# FPGA_GPIO.net
KiCad netlist of a schematic drawn in Altium Designer
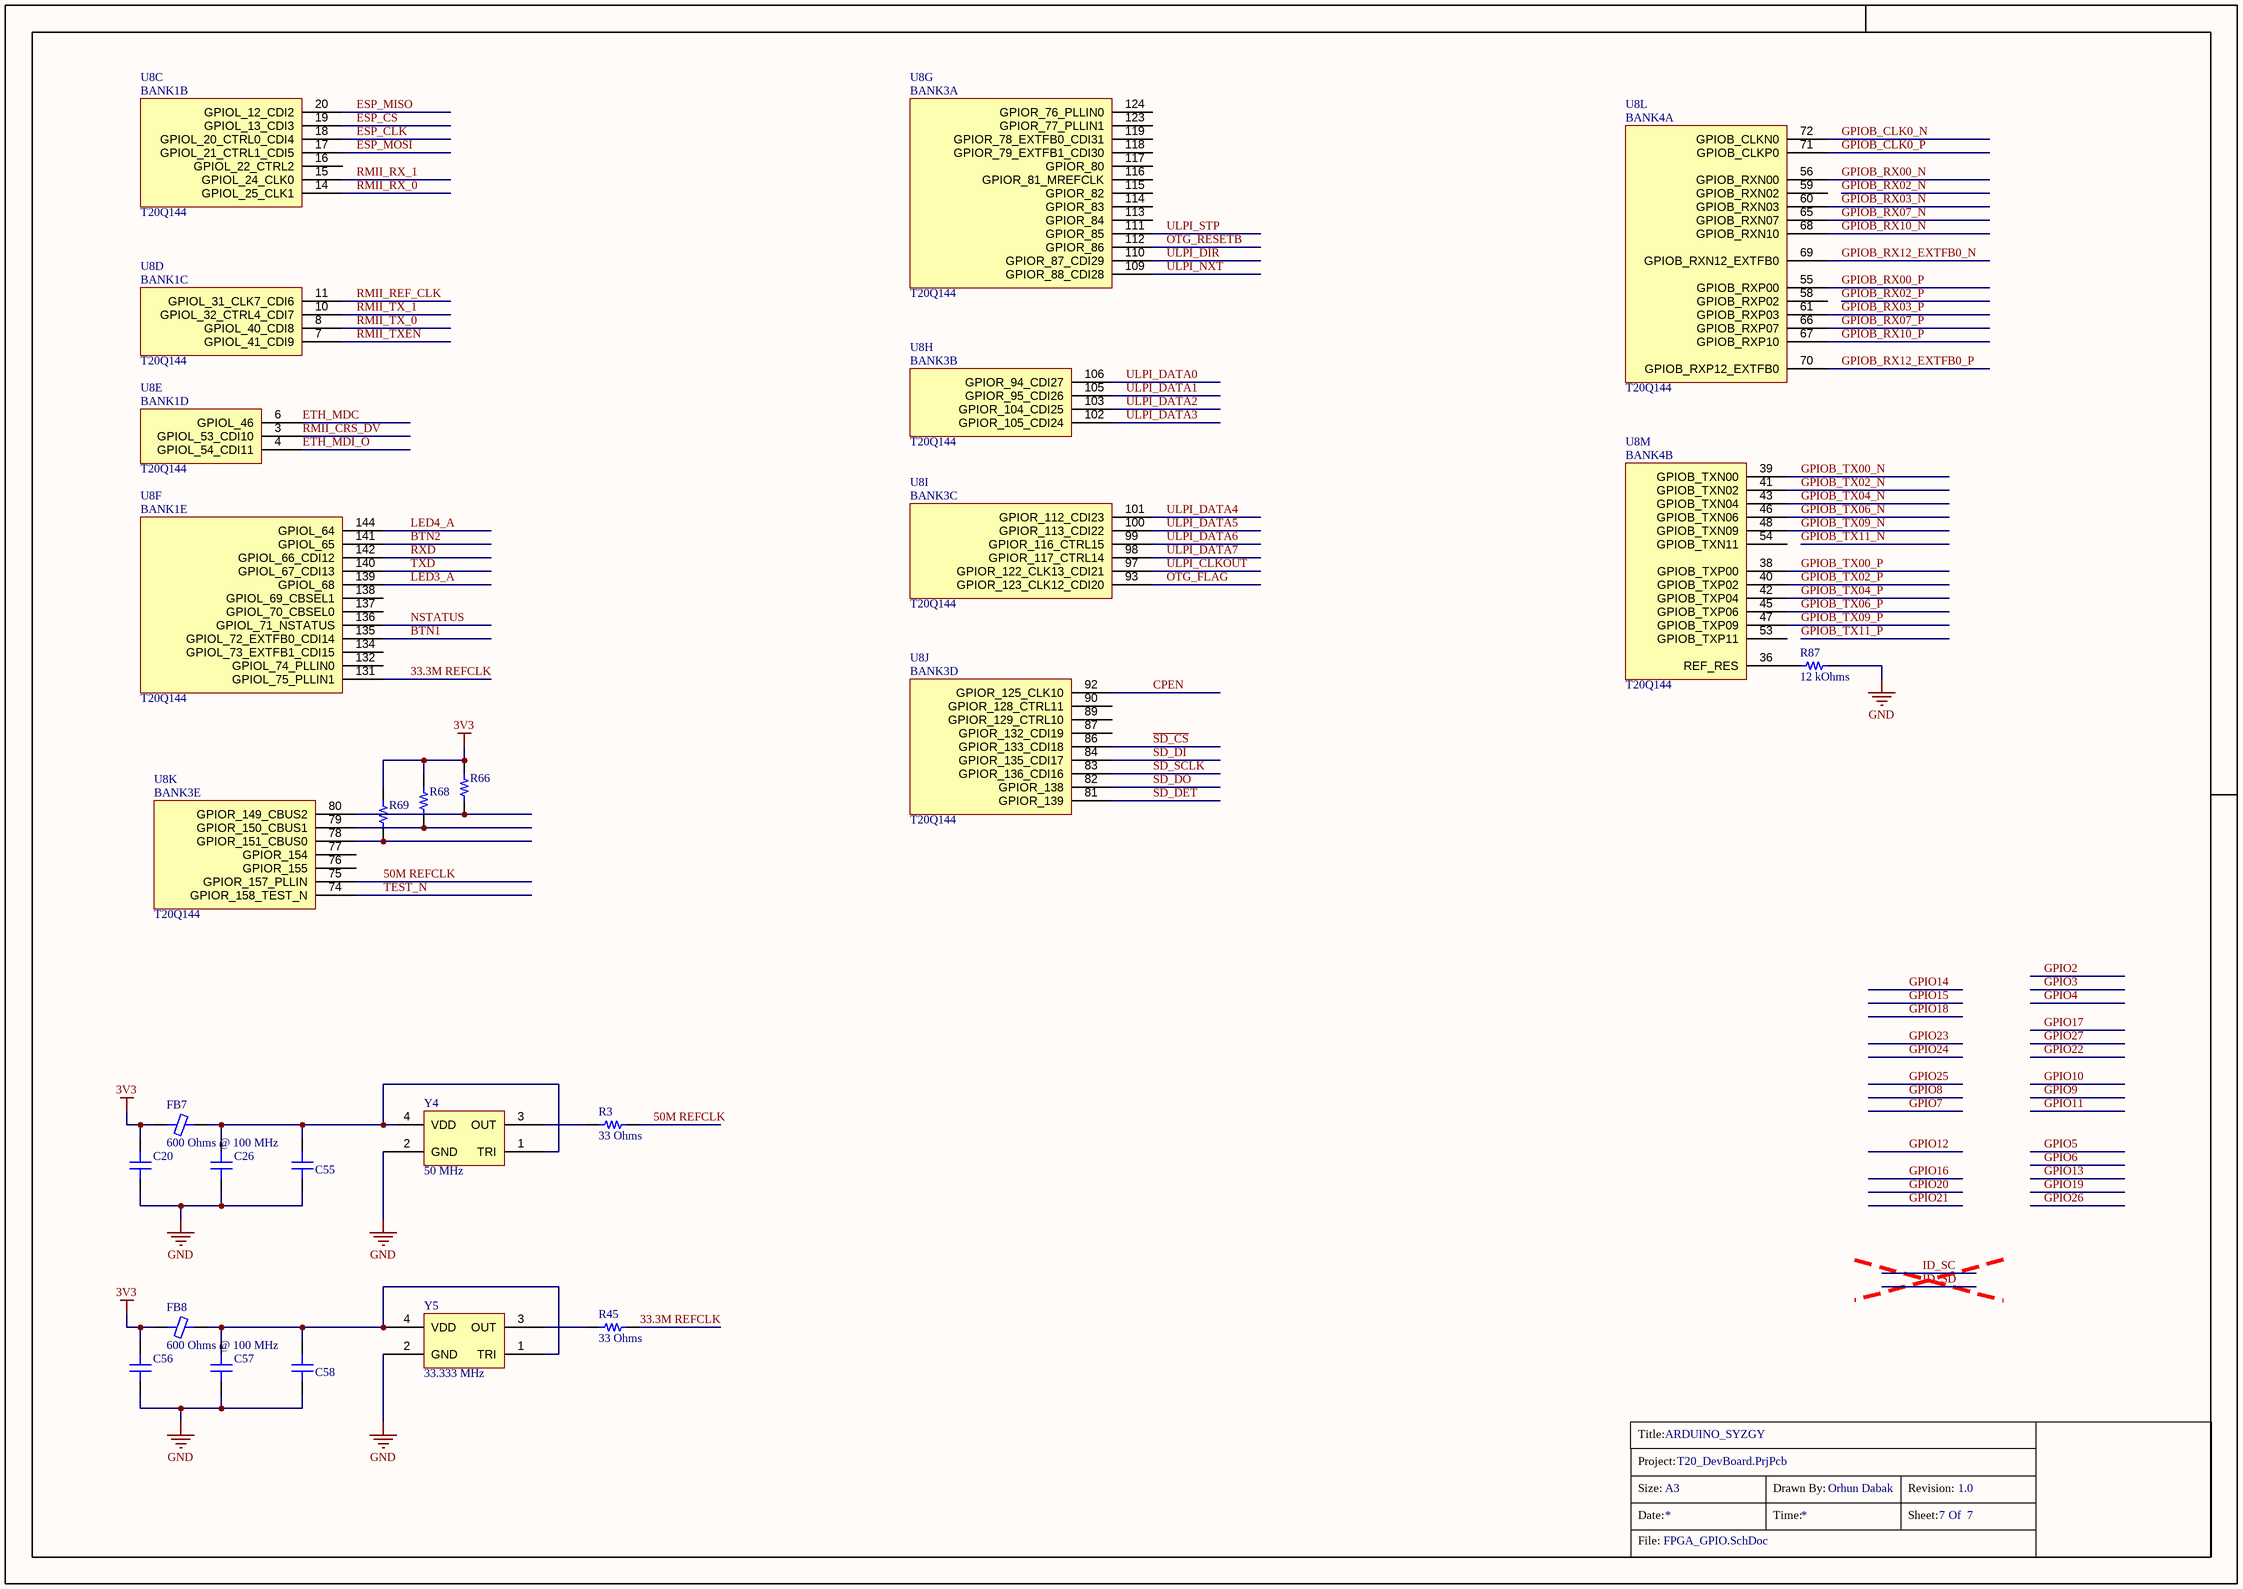
[diagram p0: FPGA_GPIO.SchDoc]

(export (version "E")
  (design (tool "Eeschema 10.0.6"))
  (components
    (comp (ref "C20")
      (value "4.7 µF")
      (footprint "CAP 0402_1005")
      (description "CAP CER 4.7UF 10V X5R 0402")
      (fields
        (field (name "PART NUMBER") "CL05A475MP5NRNC")
        (field (name "MANUFACTURER") "Samsung Electro-Mechanics")
      )
      (libsource (lib "Celestial Altium Library - altium_library") (part "Capacitor"))
    )
    (comp (ref "C26")
      (value "4.7 µF")
      (footprint "CAP 0402_1005")
      (description "CAP CER 4.7UF 10V X5R 0402")
      (fields
        (field (name "PART NUMBER") "CL05A475MP5NRNC")
        (field (name "MANUFACTURER") "Samsung Electro-Mechanics")
      )
      (libsource (lib "Celestial Altium Library - altium_library") (part "Capacitor"))
    )
    (comp (ref "C55")
      (value "10000 pF")
      (footprint "CAP 0402_1005")
      (description "CAP CER 0402 10NF 50V X7R 10%")
      (fields (field (name "PART NUMBER") "C0402C103K5RECAUTO") (field (name "MANUFACTURER") "KEMET"))
      (libsource (lib "Celestial Altium Library - altium_library") (part "Capacitor"))
    )
    (comp (ref "C56")
      (value "4.7 µF")
      (footprint "CAP 0402_1005")
      (description "CAP CER 4.7UF 10V X5R 0402")
      (fields
        (field (name "PART NUMBER") "CL05A475MP5NRNC")
        (field (name "MANUFACTURER") "Samsung Electro-Mechanics")
      )
      (libsource (lib "Celestial Altium Library - altium_library") (part "Capacitor"))
    )
    (comp (ref "C57")
      (value "4.7 µF")
      (footprint "CAP 0402_1005")
      (description "CAP CER 4.7UF 10V X5R 0402")
      (fields
        (field (name "PART NUMBER") "CL05A475MP5NRNC")
        (field (name "MANUFACTURER") "Samsung Electro-Mechanics")
      )
      (libsource (lib "Celestial Altium Library - altium_library") (part "Capacitor"))
    )
    (comp (ref "C58")
      (value "10000 pF")
      (footprint "CAP 0402_1005")
      (description "CAP CER 0402 10NF 50V X7R 10%")
      (fields (field (name "PART NUMBER") "C0402C103K5RECAUTO") (field (name "MANUFACTURER") "KEMET"))
      (libsource (lib "Celestial Altium Library - altium_library") (part "Capacitor"))
    )
    (comp (ref "FB7")
      (value "600 Ohms @ 100 MHz")
      (footprint "FER 0402_1005")
      (description "FERRITE BEAD 600 OHM 0402 1LN")
      (fields
        (field (name "PART NUMBER") "BLM15AG601SN1D")
        (field (name "MANUFACTURER") "Murata Electronics")
      )
      (libsource (lib "Celestial Altium Library - altium_library") (part "Ferrite Chip"))
    )
    (comp (ref "FB8")
      (value "600 Ohms @ 100 MHz")
      (footprint "FER 0402_1005")
      (description "FERRITE BEAD 600 OHM 0402 1LN")
      (fields
        (field (name "PART NUMBER") "BLM15AG601SN1D")
        (field (name "MANUFACTURER") "Murata Electronics")
      )
      (libsource (lib "Celestial Altium Library - altium_library") (part "Ferrite Chip"))
    )
    (comp (ref "R3")
      (value "33 Ohms")
      (footprint "RES 0402_1005")
      (description "RES 33 OHM 1% 1/16W 0402")
      (fields (field (name "PART NUMBER") "RC0402FR-0733RL") (field (name "MANUFACTURER") "Yageo"))
      (libsource (lib "Celestial Altium Library - altium_library") (part "Resistor"))
    )
    (comp (ref "R45")
      (value "33 Ohms")
      (footprint "RES 0402_1005")
      (description "RES 33 OHM 1% 1/16W 0402")
      (fields (field (name "PART NUMBER") "RC0402FR-0733RL") (field (name "MANUFACTURER") "Yageo"))
      (libsource (lib "Celestial Altium Library - altium_library") (part "Resistor"))
    )
    (comp (ref "R66")
      (value "10 kOhms")
      (footprint "RES 0402_1005")
      (description "RES 10K OHM 0.1% 1/10W 0402")
      (fields
        (field (name "PART NUMBER") "RP73PF1E10KBTD")
        (field (name "MANUFACTURER") "TE Connectivity Passive Product")
      )
      (libsource (lib "Celestial Altium Library - altium_library") (part "Resistor"))
    )
    (comp (ref "R68")
      (value "10 kOhms")
      (footprint "RES 0402_1005")
      (description "RES 10K OHM 0.1% 1/10W 0402")
      (fields
        (field (name "PART NUMBER") "RP73PF1E10KBTD")
        (field (name "MANUFACTURER") "TE Connectivity Passive Product")
      )
      (libsource (lib "Celestial Altium Library - altium_library") (part "Resistor"))
    )
    (comp (ref "R69")
      (value "10 kOhms")
      (footprint "RES 0402_1005")
      (description "RES 10K OHM 0.1% 1/10W 0402")
      (fields
        (field (name "PART NUMBER") "RP73PF1E10KBTD")
        (field (name "MANUFACTURER") "TE Connectivity Passive Product")
      )
      (libsource (lib "Celestial Altium Library - altium_library") (part "Resistor"))
    )
    (comp (ref "R87")
      (value "12 kOhms")
      (footprint "RES 0402_1005")
      (description "RES 12K OHM 1% 1/16W 0402")
      (fields
        (field (name "PART NUMBER") "RMCF0402FT12K0")
        (field (name "MANUFACTURER") "Stackpole Electronics Inc")
      )
      (libsource (lib "Celestial Altium Library - altium_library") (part "Resistor"))
    )
    (comp (ref "U8")
      (value "T20Q144")
      (footprint "T8_devkit_PCB:CQFP50P2200X2200X160-144N")
      (description "Trion® Field Programmable Gate Array (FPGA) IC 97 1044 19728 144-LQFP")
      (libsource (lib "T8_devkit_PCB") (part "T20Q144"))
    )
    (comp (ref "Y4")
      (value "50 MHz")
      (footprint "ABRACON ASE")
      (description "XTAL OSC XO 50.0000MHZ CMOS SMD")
      (fields (field (name "PART NUMBER") "ASE-50.000MHZ-ET") (field (name "MANUFACTURER") "Abracon LLC"))
      (libsource (lib "Celestial Altium Library - altium_library") (part "Abracon XO ASE"))
    )
    (comp (ref "Y5")
      (value "33.333 MHz")
      (footprint "ABRACON ASE")
      (description "XTAL OSC XO 33.3330MHZ CMOS SMD")
      (fields (field (name "PART NUMBER") "ASE-33.333MHZ-LC-T") (field (name "MANUFACTURER") "Abracon LLC"))
      (libsource (lib "Celestial Altium Library - altium_library") (part "Abracon XO ASE"))
    )
  )
  (nets
    (net (code "1") (name "/33.3M REFCLK") (class "Default")
      (node (ref "R45") (pin "2") (pinfunction "2_2") (pintype "passive"))
      (node (ref "U8") (pin "131") (pinfunction "GPIOL_75_PLLIN1_131") (pintype "passive"))
    )
    (net (code "2") (name "/50M REFCLK") (class "Default")
      (node (ref "R3") (pin "2") (pinfunction "2_2") (pintype "passive"))
      (node (ref "U8") (pin "75") (pinfunction "GPIOR_157_PLLIN_75") (pintype "passive"))
    )
    (net (code "3") (name "/BTN1") (class "Default")
      (node (ref "U8") (pin "135") (pinfunction "GPIOL_72_EXTFB0_CDI14_135") (pintype "passive"))
    )
    (net (code "4") (name "/BTN2") (class "Default")
      (node (ref "U8") (pin "141") (pinfunction "GPIOL_65_141") (pintype "passive"))
    )
    (net (code "5") (name "/CPEN") (class "Default")
      (node (ref "U8") (pin "92") (pinfunction "GPIOR_125_CLK10_92") (pintype "passive"))
    )
    (net (code "6") (name "/ESP_CLK") (class "Default")
      (node (ref "U8") (pin "18") (pinfunction "GPIOL_20_CTRL0_CDI4_18") (pintype "passive"))
    )
    (net (code "7") (name "/ESP_CS") (class "Default")
      (node (ref "U8") (pin "19") (pinfunction "GPIOL_13_CDI3_19") (pintype "passive"))
    )
    (net (code "8") (name "/ESP_MISO") (class "Default")
      (node (ref "U8") (pin "20") (pinfunction "GPIOL_12_CDI2_20") (pintype "passive"))
    )
    (net (code "9") (name "/ESP_MOSI") (class "Default")
      (node (ref "U8") (pin "17") (pinfunction "GPIOL_21_CTRL1_CDI5_17") (pintype "passive"))
    )
    (net (code "10") (name "/ETH_MDC") (class "Default")
      (node (ref "U8") (pin "6") (pinfunction "GPIOL_46_6") (pintype "passive"))
    )
    (net (code "11") (name "/ETH_MDI_O") (class "Default")
      (node (ref "U8") (pin "4") (pinfunction "GPIOL_54_CDI11_4") (pintype "passive"))
    )
    (net (code "38") (name "/GPIOB_CLK0_N") (class "Default")
      (node (ref "U8") (pin "72") (pinfunction "GPIOB_CLKN0_72") (pintype "passive"))
    )
    (net (code "39") (name "/GPIOB_CLK0_P") (class "Default")
      (node (ref "U8") (pin "71") (pinfunction "GPIOB_CLKP0_71") (pintype "passive"))
    )
    (net (code "40") (name "/GPIOB_RX00_N") (class "Default")
      (node (ref "U8") (pin "56") (pinfunction "GPIOB_RXN00_56") (pintype "passive"))
    )
    (net (code "41") (name "/GPIOB_RX00_P") (class "Default")
      (node (ref "U8") (pin "55") (pinfunction "GPIOB_RXP00_55") (pintype "passive"))
    )
    (net (code "44") (name "/GPIOB_RX03_N") (class "Default")
      (node (ref "U8") (pin "60") (pinfunction "GPIOB_RXN03_60") (pintype "passive"))
    )
    (net (code "45") (name "/GPIOB_RX03_P") (class "Default")
      (node (ref "U8") (pin "61") (pinfunction "GPIOB_RXP03_61") (pintype "passive"))
    )
    (net (code "46") (name "/GPIOB_RX07_N") (class "Default")
      (node (ref "U8") (pin "65") (pinfunction "GPIOB_RXN07_65") (pintype "passive"))
    )
    (net (code "47") (name "/GPIOB_RX07_P") (class "Default")
      (node (ref "U8") (pin "66") (pinfunction "GPIOB_RXP07_66") (pintype "passive"))
    )
    (net (code "48") (name "/GPIOB_RX10_N") (class "Default")
      (node (ref "U8") (pin "68") (pinfunction "GPIOB_RXN10_68") (pintype "passive"))
    )
    (net (code "49") (name "/GPIOB_RX10_P") (class "Default")
      (node (ref "U8") (pin "67") (pinfunction "GPIOB_RXP10_67") (pintype "passive"))
    )
    (net (code "50") (name "/GPIOB_RX12_EXTFB0_N") (class "Default")
      (node (ref "U8") (pin "69") (pinfunction "GPIOB_RXN12_EXTFB0_69") (pintype "passive"))
    )
    (net (code "51") (name "/GPIOB_RX12_EXTFB0_P") (class "Default")
      (node (ref "U8") (pin "70") (pinfunction "GPIOB_RXP12_EXTFB0_70") (pintype "passive"))
    )
    (net (code "52") (name "/GPIOB_TX00_N") (class "Default")
      (node (ref "U8") (pin "39") (pinfunction "GPIOB_TXN00_39") (pintype "passive"))
    )
    (net (code "53") (name "/GPIOB_TX00_P") (class "Default")
      (node (ref "U8") (pin "38") (pinfunction "GPIOB_TXP00_38") (pintype "passive"))
    )
    (net (code "54") (name "/GPIOB_TX02_N") (class "Default")
      (node (ref "U8") (pin "41") (pinfunction "GPIOB_TXN02_41") (pintype "passive"))
    )
    (net (code "55") (name "/GPIOB_TX02_P") (class "Default")
      (node (ref "U8") (pin "40") (pinfunction "GPIOB_TXP02_40") (pintype "passive"))
    )
    (net (code "56") (name "/GPIOB_TX04_N") (class "Default")
      (node (ref "U8") (pin "43") (pinfunction "GPIOB_TXN04_43") (pintype "passive"))
    )
    (net (code "57") (name "/GPIOB_TX04_P") (class "Default")
      (node (ref "U8") (pin "42") (pinfunction "GPIOB_TXP04_42") (pintype "passive"))
    )
    (net (code "58") (name "/GPIOB_TX06_N") (class "Default")
      (node (ref "U8") (pin "46") (pinfunction "GPIOB_TXN06_46") (pintype "passive"))
    )
    (net (code "59") (name "/GPIOB_TX06_P") (class "Default")
      (node (ref "U8") (pin "45") (pinfunction "GPIOB_TXP06_45") (pintype "passive"))
    )
    (net (code "60") (name "/GPIOB_TX09_N") (class "Default")
      (node (ref "U8") (pin "48") (pinfunction "GPIOB_TXN09_48") (pintype "passive"))
    )
    (net (code "61") (name "/GPIOB_TX09_P") (class "Default")
      (node (ref "U8") (pin "47") (pinfunction "GPIOB_TXP09_47") (pintype "passive"))
    )
    (net (code "66") (name "/LED3_A") (class "Default")
      (node (ref "U8") (pin "139") (pinfunction "GPIOL_68_139") (pintype "passive"))
    )
    (net (code "67") (name "/LED4_A") (class "Default")
      (node (ref "U8") (pin "144") (pinfunction "GPIOL_64_144") (pintype "passive"))
    )
    (net (code "68") (name "/NSTATUS") (class "Default")
      (node (ref "U8") (pin "136") (pinfunction "GPIOL_71_NSTATUS_136") (pintype "passive"))
    )
    (net (code "69") (name "/OTG_FLAG") (class "Default")
      (node (ref "U8") (pin "93") (pinfunction "GPIOR_123_CLK12_CDI20_93") (pintype "passive"))
    )
    (net (code "70") (name "/OTG_RESETB") (class "Default")
      (node (ref "U8") (pin "112") (pinfunction "GPIOR_86_112") (pintype "passive"))
    )
    (net (code "71") (name "/RMII_CRS_DV") (class "Default")
      (node (ref "U8") (pin "3") (pinfunction "GPIOL_53_CDI10_3") (pintype "passive"))
    )
    (net (code "72") (name "/RMII_REF_CLK") (class "Default")
      (node (ref "U8") (pin "11") (pinfunction "GPIOL_31_CLK7_CDI6_11") (pintype "passive"))
    )
    (net (code "73") (name "/RMII_RX_0") (class "Default")
      (node (ref "U8") (pin "14") (pinfunction "GPIOL_25_CLK1_14") (pintype "passive"))
    )
    (net (code "74") (name "/RMII_RX_1") (class "Default")
      (node (ref "U8") (pin "15") (pinfunction "GPIOL_24_CLK0_15") (pintype "passive"))
    )
    (net (code "75") (name "/RMII_TXEN") (class "Default")
      (node (ref "U8") (pin "7") (pinfunction "GPIOL_41_CDI9_7") (pintype "passive"))
    )
    (net (code "76") (name "/RMII_TX_0") (class "Default")
      (node (ref "U8") (pin "8") (pinfunction "GPIOL_40_CDI8_8") (pintype "passive"))
    )
    (net (code "77") (name "/RMII_TX_1") (class "Default")
      (node (ref "U8") (pin "10") (pinfunction "GPIOL_32_CTRL4_CDI7_10") (pintype "passive"))
    )
    (net (code "78") (name "/RXD") (class "Default")
      (node (ref "U8") (pin "142") (pinfunction "GPIOL_66_CDI12_142") (pintype "passive"))
    )
    (net (code "79") (name "/SD_DI") (class "Default")
      (node (ref "U8") (pin "84") (pinfunction "GPIOR_135_CDI17_84") (pintype "passive"))
    )
    (net (code "80") (name "/SD_DO") (class "Default")
      (node (ref "U8") (pin "82") (pinfunction "GPIOR_138_82") (pintype "passive"))
    )
    (net (code "81") (name "/SD_SCLK") (class "Default")
      (node (ref "U8") (pin "83") (pinfunction "GPIOR_136_CDI16_83") (pintype "passive"))
    )
    (net (code "82") (name "/TEST_N") (class "Default")
      (node (ref "U8") (pin "74") (pinfunction "GPIOR_158_TEST_N_74") (pintype "passive"))
    )
    (net (code "83") (name "/TXD") (class "Default")
      (node (ref "U8") (pin "140") (pinfunction "GPIOL_67_CDI13_140") (pintype "passive"))
    )
    (net (code "84") (name "/ULPI_CLKOUT") (class "Default")
      (node (ref "U8") (pin "97") (pinfunction "GPIOR_122_CLK13_CDI21_97") (pintype "passive"))
    )
    (net (code "85") (name "/ULPI_DATA0") (class "Default")
      (node (ref "U8") (pin "106") (pinfunction "GPIOR_94_CDI27_106") (pintype "passive"))
    )
    (net (code "86") (name "/ULPI_DATA1") (class "Default")
      (node (ref "U8") (pin "105") (pinfunction "GPIOR_95_CDI26_105") (pintype "passive"))
    )
    (net (code "87") (name "/ULPI_DATA2") (class "Default")
      (node (ref "U8") (pin "103") (pinfunction "GPIOR_104_CDI25_103") (pintype "passive"))
    )
    (net (code "88") (name "/ULPI_DATA3") (class "Default")
      (node (ref "U8") (pin "102") (pinfunction "GPIOR_105_CDI24_102") (pintype "passive"))
    )
    (net (code "89") (name "/ULPI_DATA4") (class "Default")
      (node (ref "U8") (pin "101") (pinfunction "GPIOR_112_CDI23_101") (pintype "passive"))
    )
    (net (code "90") (name "/ULPI_DATA5") (class "Default")
      (node (ref "U8") (pin "100") (pinfunction "GPIOR_113_CDI22_100") (pintype "passive"))
    )
    (net (code "91") (name "/ULPI_DATA6") (class "Default")
      (node (ref "U8") (pin "99") (pinfunction "GPIOR_116_CTRL15_99") (pintype "passive"))
    )
    (net (code "92") (name "/ULPI_DATA7") (class "Default")
      (node (ref "U8") (pin "98") (pinfunction "GPIOR_117_CTRL14_98") (pintype "passive"))
    )
    (net (code "93") (name "/ULPI_DIR") (class "Default")
      (node (ref "U8") (pin "110") (pinfunction "GPIOR_87_CDI29_110") (pintype "passive"))
    )
    (net (code "94") (name "/ULPI_NXT") (class "Default")
      (node (ref "U8") (pin "109") (pinfunction "GPIOR_88_CDI28_109") (pintype "passive"))
    )
    (net (code "95") (name "/ULPI_STP") (class "Default")
      (node (ref "U8") (pin "111") (pinfunction "GPIOR_85_111") (pintype "passive"))
    )
    (net (code "96") (name "/~{SD_CS}") (class "Default")
      (node (ref "U8") (pin "86") (pinfunction "GPIOR_133_CDI18_86") (pintype "passive"))
    )
    (net (code "97") (name "/~{SD_DET}") (class "Default")
      (node (ref "U8") (pin "81") (pinfunction "GPIOR_139_81") (pintype "passive"))
    )
    (net (code "98") (name "3V3") (class "Default")
      (node (ref "C20") (pin "2") (pinfunction "2_2") (pintype "passive"))
      (node (ref "C56") (pin "2") (pinfunction "2_2") (pintype "passive"))
      (node (ref "FB7") (pin "1") (pinfunction "1_1") (pintype "passive"))
      (node (ref "FB8") (pin "1") (pinfunction "1_1") (pintype "passive"))
      (node (ref "R66") (pin "2") (pinfunction "2_2") (pintype "passive"))
      (node (ref "R68") (pin "2") (pinfunction "2_2") (pintype "passive"))
      (node (ref "R69") (pin "2") (pinfunction "2_2") (pintype "passive"))
    )
    (net (code "99") (name "GND") (class "Default")
      (node (ref "C20") (pin "1") (pinfunction "1_1") (pintype "passive"))
      (node (ref "C26") (pin "1") (pinfunction "1_1") (pintype "passive"))
      (node (ref "C55") (pin "1") (pinfunction "1_1") (pintype "passive"))
      (node (ref "C56") (pin "1") (pinfunction "1_1") (pintype "passive"))
      (node (ref "C57") (pin "1") (pinfunction "1_1") (pintype "passive"))
      (node (ref "C58") (pin "1") (pinfunction "1_1") (pintype "passive"))
      (node (ref "R87") (pin "2") (pinfunction "2_2") (pintype "passive"))
      (node (ref "Y4") (pin "2") (pinfunction "GND_2") (pintype "passive"))
      (node (ref "Y5") (pin "2") (pinfunction "GND_2") (pintype "passive"))
    )
    (net (code "100") (name "Net-(U8K-GPIOR_149_CBUS2)") (class "Default")
      (node (ref "R66") (pin "1") (pinfunction "1_1") (pintype "passive"))
      (node (ref "U8") (pin "80") (pinfunction "GPIOR_149_CBUS2_80") (pintype "passive"))
    )
    (net (code "101") (name "Net-(U8K-GPIOR_150_CBUS1)") (class "Default")
      (node (ref "R68") (pin "1") (pinfunction "1_1") (pintype "passive"))
      (node (ref "U8") (pin "79") (pinfunction "GPIOR_150_CBUS1_79") (pintype "passive"))
    )
    (net (code "102") (name "Net-(U8K-GPIOR_151_CBUS0)") (class "Default")
      (node (ref "R69") (pin "1") (pinfunction "1_1") (pintype "passive"))
      (node (ref "U8") (pin "78") (pinfunction "GPIOR_151_CBUS0_78") (pintype "passive"))
    )
    (net (code "103") (name "Net-(U8M-REF_RES)") (class "Default")
      (node (ref "R87") (pin "1") (pinfunction "1_1") (pintype "passive"))
      (node (ref "U8") (pin "36") (pinfunction "REF_RES_36") (pintype "passive"))
    )
    (net (code "104") (name "Net-(Y4-OUT)") (class "Default")
      (node (ref "R3") (pin "1") (pinfunction "1_1") (pintype "passive"))
      (node (ref "Y4") (pin "3") (pinfunction "OUT_3") (pintype "passive"))
    )
    (net (code "105") (name "Net-(Y4-TRI)") (class "Default")
      (node (ref "C26") (pin "2") (pinfunction "2_2") (pintype "passive"))
      (node (ref "C55") (pin "2") (pinfunction "2_2") (pintype "passive"))
      (node (ref "FB7") (pin "2") (pinfunction "2_2") (pintype "passive"))
      (node (ref "Y4") (pin "1") (pinfunction "TRI_1") (pintype "passive"))
      (node (ref "Y4") (pin "4") (pinfunction "VDD_4") (pintype "passive"))
    )
    (net (code "106") (name "Net-(Y5-OUT)") (class "Default")
      (node (ref "R45") (pin "1") (pinfunction "1_1") (pintype "passive"))
      (node (ref "Y5") (pin "3") (pinfunction "OUT_3") (pintype "passive"))
    )
    (net (code "107") (name "Net-(Y5-TRI)") (class "Default")
      (node (ref "C57") (pin "2") (pinfunction "2_2") (pintype "passive"))
      (node (ref "C58") (pin "2") (pinfunction "2_2") (pintype "passive"))
      (node (ref "FB8") (pin "2") (pinfunction "2_2") (pintype "passive"))
      (node (ref "Y5") (pin "1") (pinfunction "TRI_1") (pintype "passive"))
      (node (ref "Y5") (pin "4") (pinfunction "VDD_4") (pintype "passive"))
    )
    (net (code "108") (name "unconnected-(U8C-GPIOL_22_CTRL2-Pad16)") (class "Default")
      (node (ref "U8") (pin "16") (pinfunction "GPIOL_22_CTRL2_16") (pintype "passive"))
    )
    (net (code "109") (name "unconnected-(U8F-GPIOL_69_CBSEL1-Pad138)") (class "Default")
      (node (ref "U8") (pin "138") (pinfunction "GPIOL_69_CBSEL1_138") (pintype "passive"))
    )
    (net (code "110") (name "unconnected-(U8F-GPIOL_70_CBSEL0-Pad137)") (class "Default")
      (node (ref "U8") (pin "137") (pinfunction "GPIOL_70_CBSEL0_137") (pintype "passive"))
    )
    (net (code "111") (name "unconnected-(U8F-GPIOL_73_EXTFB1_CDI15-Pad134)") (class "Default")
      (node (ref "U8") (pin "134") (pinfunction "GPIOL_73_EXTFB1_CDI15_134") (pintype "passive"))
    )
    (net (code "112") (name "unconnected-(U8F-GPIOL_74_PLLIN0-Pad132)") (class "Default")
      (node (ref "U8") (pin "132") (pinfunction "GPIOL_74_PLLIN0_132") (pintype "passive"))
    )
    (net (code "113") (name "unconnected-(U8G-GPIOR_76_PLLIN0-Pad124)") (class "Default")
      (node (ref "U8") (pin "124") (pinfunction "GPIOR_76_PLLIN0_124") (pintype "passive"))
    )
    (net (code "114") (name "unconnected-(U8G-GPIOR_77_PLLIN1-Pad123)") (class "Default")
      (node (ref "U8") (pin "123") (pinfunction "GPIOR_77_PLLIN1_123") (pintype "passive"))
    )
    (net (code "115") (name "unconnected-(U8G-GPIOR_78_EXTFB0_CDI31-Pad119)") (class "Default")
      (node (ref "U8") (pin "119") (pinfunction "GPIOR_78_EXTFB0_CDI31_119") (pintype "passive"))
    )
    (net (code "116") (name "unconnected-(U8G-GPIOR_79_EXTFB1_CDI30-Pad118)") (class "Default")
      (node (ref "U8") (pin "118") (pinfunction "GPIOR_79_EXTFB1_CDI30_118") (pintype "passive"))
    )
    (net (code "117") (name "unconnected-(U8G-GPIOR_80-Pad117)") (class "Default")
      (node (ref "U8") (pin "117") (pinfunction "GPIOR_80_117") (pintype "passive"))
    )
    (net (code "118") (name "unconnected-(U8G-GPIOR_81_MREFCLK-Pad116)") (class "Default")
      (node (ref "U8") (pin "116") (pinfunction "GPIOR_81_MREFCLK_116") (pintype "passive"))
    )
    (net (code "119") (name "unconnected-(U8G-GPIOR_82-Pad115)") (class "Default")
      (node (ref "U8") (pin "115") (pinfunction "GPIOR_82_115") (pintype "passive"))
    )
    (net (code "120") (name "unconnected-(U8G-GPIOR_83-Pad114)") (class "Default")
      (node (ref "U8") (pin "114") (pinfunction "GPIOR_83_114") (pintype "passive"))
    )
    (net (code "121") (name "unconnected-(U8G-GPIOR_84-Pad113)") (class "Default")
      (node (ref "U8") (pin "113") (pinfunction "GPIOR_84_113") (pintype "passive"))
    )
    (net (code "122") (name "unconnected-(U8J-GPIOR_128_CTRL11-Pad90)") (class "Default")
      (node (ref "U8") (pin "90") (pinfunction "GPIOR_128_CTRL11_90") (pintype "passive"))
    )
    (net (code "123") (name "unconnected-(U8J-GPIOR_129_CTRL10-Pad89)") (class "Default")
      (node (ref "U8") (pin "89") (pinfunction "GPIOR_129_CTRL10_89") (pintype "passive"))
    )
    (net (code "124") (name "unconnected-(U8J-GPIOR_132_CDI19-Pad87)") (class "Default")
      (node (ref "U8") (pin "87") (pinfunction "GPIOR_132_CDI19_87") (pintype "passive"))
    )
    (net (code "125") (name "unconnected-(U8K-GPIOR_154-Pad77)") (class "Default")
      (node (ref "U8") (pin "77") (pinfunction "GPIOR_154_77") (pintype "passive"))
    )
    (net (code "126") (name "unconnected-(U8K-GPIOR_155-Pad76)") (class "Default")
      (node (ref "U8") (pin "76") (pinfunction "GPIOR_155_76") (pintype "passive"))
    )
    (net (code "127") (name "unconnected-(U8L-GPIOB_RXN02-Pad59)") (class "Default")
      (node (ref "U8") (pin "59") (pinfunction "GPIOB_RXN02_59") (pintype "passive"))
    )
    (net (code "128") (name "unconnected-(U8L-GPIOB_RXP02-Pad58)") (class "Default")
      (node (ref "U8") (pin "58") (pinfunction "GPIOB_RXP02_58") (pintype "passive"))
    )
    (net (code "129") (name "unconnected-(U8M-GPIOB_TXN11-Pad54)") (class "Default")
      (node (ref "U8") (pin "54") (pinfunction "GPIOB_TXN11_54") (pintype "passive"))
    )
    (net (code "130") (name "unconnected-(U8M-GPIOB_TXP11-Pad53)") (class "Default")
      (node (ref "U8") (pin "53") (pinfunction "GPIOB_TXP11_53") (pintype "passive"))
    )
  )
)
